# dds_ad9958.net
KiCad netlist of a schematic drawn in EAGLE
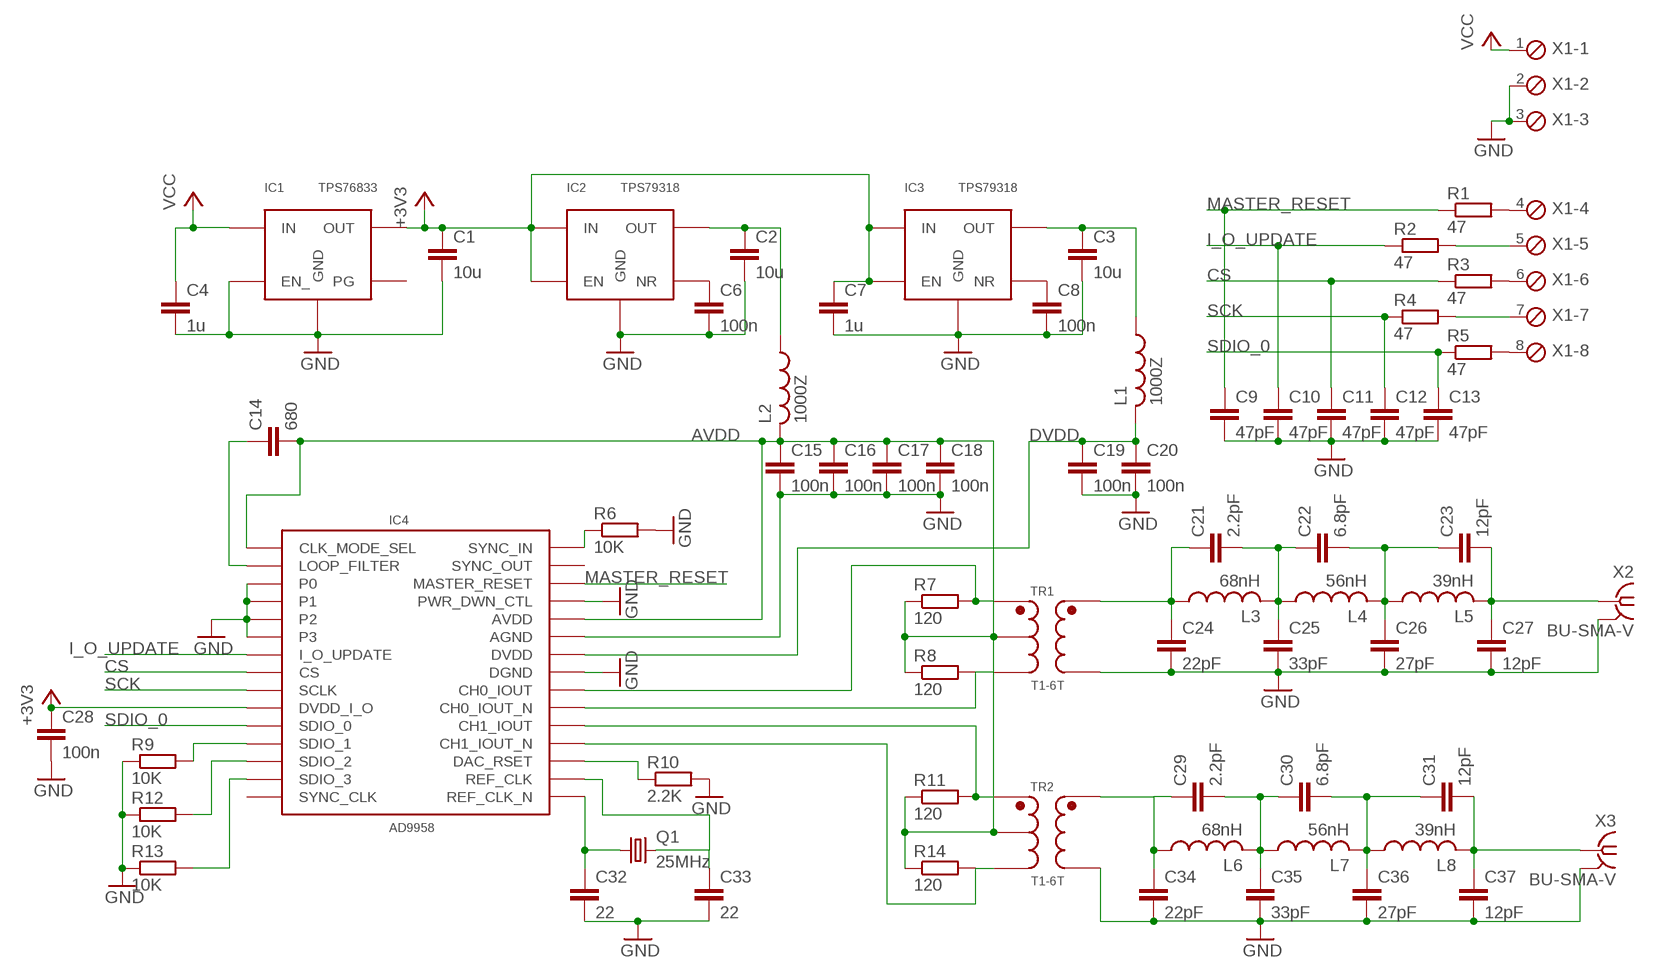
[diagram p0: schematic, sheet 1]

(export (version "E")
  (design (tool "Eeschema 10.0.6"))
  (components
    (comp (ref "C1")
      (value "10u")
      (footprint "eagle-import:C0805")
      (libsource (lib "eagle-import") (part "C-EUC0805"))
    )
    (comp (ref "C2")
      (value "10u")
      (footprint "eagle-import:C0805")
      (libsource (lib "eagle-import") (part "C-EUC0805"))
    )
    (comp (ref "C3")
      (value "10u")
      (footprint "eagle-import:C0805")
      (libsource (lib "eagle-import") (part "C-EUC0805"))
    )
    (comp (ref "C4")
      (value "1u")
      (footprint "eagle-import:C0603")
      (libsource (lib "eagle-import") (part "C-EUC0603"))
    )
    (comp (ref "C6")
      (value "100n")
      (footprint "eagle-import:C0603")
      (libsource (lib "eagle-import") (part "C-EUC0603"))
    )
    (comp (ref "C7")
      (value "1u")
      (footprint "eagle-import:C0603")
      (libsource (lib "eagle-import") (part "C-EUC0603"))
    )
    (comp (ref "C8")
      (value "100n")
      (footprint "eagle-import:C0603")
      (libsource (lib "eagle-import") (part "C-EUC0603"))
    )
    (comp (ref "C9")
      (value "47pF")
      (footprint "eagle-import:C0805")
      (libsource (lib "eagle-import") (part "C-EUC0805"))
    )
    (comp (ref "C10")
      (value "47pF")
      (footprint "eagle-import:C0805")
      (libsource (lib "eagle-import") (part "C-EUC0805"))
    )
    (comp (ref "C11")
      (value "47pF")
      (footprint "eagle-import:C0805")
      (libsource (lib "eagle-import") (part "C-EUC0805"))
    )
    (comp (ref "C12")
      (value "47pF")
      (footprint "eagle-import:C0805")
      (libsource (lib "eagle-import") (part "C-EUC0805"))
    )
    (comp (ref "C13")
      (value "47pF")
      (footprint "eagle-import:C0805")
      (libsource (lib "eagle-import") (part "C-EUC0805"))
    )
    (comp (ref "C14")
      (value "680")
      (footprint "eagle-import:C0805")
      (libsource (lib "eagle-import") (part "C-EUC0805"))
    )
    (comp (ref "C15")
      (value "100n")
      (footprint "eagle-import:C0603")
      (libsource (lib "eagle-import") (part "C-EUC0603"))
    )
    (comp (ref "C16")
      (value "100n")
      (footprint "eagle-import:C0603")
      (libsource (lib "eagle-import") (part "C-EUC0603"))
    )
    (comp (ref "C17")
      (value "100n")
      (footprint "eagle-import:C0603")
      (libsource (lib "eagle-import") (part "C-EUC0603"))
    )
    (comp (ref "C18")
      (value "100n")
      (footprint "eagle-import:C0603")
      (libsource (lib "eagle-import") (part "C-EUC0603"))
    )
    (comp (ref "C19")
      (value "100n")
      (footprint "eagle-import:C0603")
      (libsource (lib "eagle-import") (part "C-EUC0603"))
    )
    (comp (ref "C20")
      (value "100n")
      (footprint "eagle-import:C0603")
      (libsource (lib "eagle-import") (part "C-EUC0603"))
    )
    (comp (ref "C21")
      (value "2.2pF")
      (footprint "eagle-import:C0805")
      (libsource (lib "eagle-import") (part "C-EUC0805"))
    )
    (comp (ref "C22")
      (value "6.8pF")
      (footprint "eagle-import:C0805")
      (libsource (lib "eagle-import") (part "C-EUC0805"))
    )
    (comp (ref "C23")
      (value "12pF")
      (footprint "eagle-import:C0805")
      (libsource (lib "eagle-import") (part "C-EUC0805"))
    )
    (comp (ref "C24")
      (value "22pF")
      (footprint "eagle-import:C0805")
      (libsource (lib "eagle-import") (part "C-EUC0805"))
    )
    (comp (ref "C25")
      (value "33pF")
      (footprint "eagle-import:C0805")
      (libsource (lib "eagle-import") (part "C-EUC0805"))
    )
    (comp (ref "C26")
      (value "27pF")
      (footprint "eagle-import:C0805")
      (libsource (lib "eagle-import") (part "C-EUC0805"))
    )
    (comp (ref "C27")
      (value "12pF")
      (footprint "eagle-import:C0805")
      (libsource (lib "eagle-import") (part "C-EUC0805"))
    )
    (comp (ref "C28")
      (value "100n")
      (footprint "eagle-import:C0603")
      (libsource (lib "eagle-import") (part "C-EUC0603"))
    )
    (comp (ref "C29")
      (value "2.2pF")
      (footprint "eagle-import:C0805")
      (libsource (lib "eagle-import") (part "C-EUC0805"))
    )
    (comp (ref "C30")
      (value "6.8pF")
      (footprint "eagle-import:C0805")
      (libsource (lib "eagle-import") (part "C-EUC0805"))
    )
    (comp (ref "C31")
      (value "12pF")
      (footprint "eagle-import:C0805")
      (libsource (lib "eagle-import") (part "C-EUC0805"))
    )
    (comp (ref "C32")
      (value "22")
      (footprint "eagle-import:C0603")
      (libsource (lib "eagle-import") (part "C-EUC0603"))
    )
    (comp (ref "C33")
      (value "22")
      (footprint "eagle-import:C0603")
      (libsource (lib "eagle-import") (part "C-EUC0603"))
    )
    (comp (ref "C34")
      (value "22pF")
      (footprint "eagle-import:C0805")
      (libsource (lib "eagle-import") (part "C-EUC0805"))
    )
    (comp (ref "C35")
      (value "33pF")
      (footprint "eagle-import:C0805")
      (libsource (lib "eagle-import") (part "C-EUC0805"))
    )
    (comp (ref "C36")
      (value "27pF")
      (footprint "eagle-import:C0805")
      (libsource (lib "eagle-import") (part "C-EUC0805"))
    )
    (comp (ref "C37")
      (value "12pF")
      (footprint "eagle-import:C0805")
      (libsource (lib "eagle-import") (part "C-EUC0805"))
    )
    (comp (ref "IC1")
      (value "TPS76833")
      (footprint "eagle-import:SO8")
      (libsource (lib "eagle-import") (part "TPS768XX"))
    )
    (comp (ref "IC2")
      (value "TPS79318")
      (footprint "eagle-import:SOT23-5")
      (libsource (lib "eagle-import") (part "TPS793XX_FIXED"))
    )
    (comp (ref "IC3")
      (value "TPS79318")
      (footprint "eagle-import:SOT23-5")
      (libsource (lib "eagle-import") (part "TPS793XX_FIXED"))
    )
    (comp (ref "IC4")
      (value "AD9958")
      (footprint "eagle-import:CP-56-1")
      (libsource (lib "eagle-import") (part "AD9958"))
    )
    (comp (ref "L1")
      (value "1000Z")
      (footprint "eagle-import:L3225P")
      (libsource (lib "eagle-import") (part "L-USL3225P"))
    )
    (comp (ref "L2")
      (value "1000Z")
      (footprint "eagle-import:L3225P")
      (libsource (lib "eagle-import") (part "L-USL3225P"))
    )
    (comp (ref "L3")
      (value "68nH")
      (footprint "eagle-import:C0805")
      (libsource (lib "eagle-import") (part "L-USL0805"))
    )
    (comp (ref "L4")
      (value "56nH")
      (footprint "eagle-import:C0805")
      (libsource (lib "eagle-import") (part "L-USL0805"))
    )
    (comp (ref "L5")
      (value "39nH")
      (footprint "eagle-import:C0805")
      (libsource (lib "eagle-import") (part "L-USL0805"))
    )
    (comp (ref "L6")
      (value "68nH")
      (footprint "eagle-import:C0805")
      (libsource (lib "eagle-import") (part "L-USL0805"))
    )
    (comp (ref "L7")
      (value "56nH")
      (footprint "eagle-import:C0805")
      (libsource (lib "eagle-import") (part "L-USL0805"))
    )
    (comp (ref "L8")
      (value "39nH")
      (footprint "eagle-import:C0805")
      (libsource (lib "eagle-import") (part "L-USL0805"))
    )
    (comp (ref "Q1")
      (value "25MHz")
      (footprint "eagle-import:HC49_S")
      (libsource (lib "eagle-import") (part "CRYSTALHC49S"))
    )
    (comp (ref "R1")
      (value "47")
      (footprint "eagle-import:R0603")
      (libsource (lib "eagle-import") (part "R-EU_R0603"))
    )
    (comp (ref "R2")
      (value "47")
      (footprint "eagle-import:R0603")
      (libsource (lib "eagle-import") (part "R-EU_R0603"))
    )
    (comp (ref "R3")
      (value "47")
      (footprint "eagle-import:R0603")
      (libsource (lib "eagle-import") (part "R-EU_R0603"))
    )
    (comp (ref "R4")
      (value "47")
      (footprint "eagle-import:R0603")
      (libsource (lib "eagle-import") (part "R-EU_R0603"))
    )
    (comp (ref "R5")
      (value "47")
      (footprint "eagle-import:R0603")
      (libsource (lib "eagle-import") (part "R-EU_R0603"))
    )
    (comp (ref "R6")
      (value "10K")
      (footprint "eagle-import:R0603")
      (libsource (lib "eagle-import") (part "R-EU_R0603"))
    )
    (comp (ref "R7")
      (value "120")
      (footprint "eagle-import:R0603")
      (libsource (lib "eagle-import") (part "R-EU_R0603"))
    )
    (comp (ref "R8")
      (value "120")
      (footprint "eagle-import:R0603")
      (libsource (lib "eagle-import") (part "R-EU_R0603"))
    )
    (comp (ref "R9")
      (value "10K")
      (footprint "eagle-import:R0603")
      (libsource (lib "eagle-import") (part "R-EU_R0603"))
    )
    (comp (ref "R10")
      (value "2.2K")
      (footprint "eagle-import:R0603")
      (libsource (lib "eagle-import") (part "R-EU_R0603"))
    )
    (comp (ref "R11")
      (value "120")
      (footprint "eagle-import:R0603")
      (libsource (lib "eagle-import") (part "R-EU_R0603"))
    )
    (comp (ref "R12")
      (value "10K")
      (footprint "eagle-import:R0603")
      (libsource (lib "eagle-import") (part "R-EU_R0603"))
    )
    (comp (ref "R13")
      (value "10K")
      (footprint "eagle-import:R0603")
      (libsource (lib "eagle-import") (part "R-EU_R0603"))
    )
    (comp (ref "R14")
      (value "120")
      (footprint "eagle-import:R0603")
      (libsource (lib "eagle-import") (part "R-EU_R0603"))
    )
    (comp (ref "TR1")
      (value "T1-6T")
      (footprint "eagle-import:KK81")
      (libsource (lib "eagle-import") (part "T1-6T"))
    )
    (comp (ref "TR2")
      (value "T1-6T")
      (footprint "eagle-import:KK81")
      (libsource (lib "eagle-import") (part "T1-6T"))
    )
    (comp (ref "X1")
      (value "MPT8")
      (footprint "eagle-import:8POL254")
      (libsource (lib "eagle-import") (part "MPT8"))
    )
    (comp (ref "X2")
      (value "BU-SMA-V")
      (footprint "eagle-import:BU-SMA-V")
      (libsource (lib "eagle-import") (part "BU-SMA-V"))
    )
    (comp (ref "X3")
      (value "BU-SMA-V")
      (footprint "eagle-import:BU-SMA-V")
      (libsource (lib "eagle-import") (part "BU-SMA-V"))
    )
  )
  (nets
    (net (code "1") (name "+3V3") (class "Default")
      (node (ref "C1") (pin "1") (pinfunction "1_1") (pintype "passive"))
      (node (ref "C28") (pin "1") (pinfunction "1_1") (pintype "passive"))
      (node (ref "C7") (pin "1") (pinfunction "1_1") (pintype "passive"))
      (node (ref "IC1") (pin "5") (pinfunction "OUT_5") (pintype "bidirectional"))
      (node (ref "IC1") (pin "6") (pinfunction "OUT_6") (pintype "bidirectional"))
      (node (ref "IC2") (pin "1") (pinfunction "IN_1") (pintype "bidirectional"))
      (node (ref "IC2") (pin "3") (pinfunction "EN_3") (pintype "bidirectional"))
      (node (ref "IC3") (pin "1") (pinfunction "IN_1") (pintype "bidirectional"))
      (node (ref "IC3") (pin "3") (pinfunction "EN_3") (pintype "bidirectional"))
      (node (ref "IC4") (pin "P$49") (pinfunction "DVDD_I_O_P$49") (pintype "bidirectional"))
    )
    (net (code "2") (name "/AVDD") (class "Default")
      (node (ref "C14") (pin "2") (pinfunction "2_2") (pintype "passive"))
      (node (ref "C15") (pin "1") (pinfunction "1_1") (pintype "passive"))
      (node (ref "C16") (pin "1") (pinfunction "1_1") (pintype "passive"))
      (node (ref "C17") (pin "1") (pinfunction "1_1") (pintype "passive"))
      (node (ref "C18") (pin "1") (pinfunction "1_1") (pintype "passive"))
      (node (ref "IC4") (pin "P$11") (pinfunction "AVDD_P$11") (pintype "bidirectional"))
      (node (ref "IC4") (pin "P$15") (pinfunction "AVDD_P$15") (pintype "bidirectional"))
      (node (ref "IC4") (pin "P$19") (pinfunction "AVDD_P$19") (pintype "bidirectional"))
      (node (ref "IC4") (pin "P$21") (pinfunction "AVDD_P$21") (pintype "bidirectional"))
      (node (ref "IC4") (pin "P$24") (pinfunction "CLK_MODE_SEL_P$24") (pintype "bidirectional"))
      (node (ref "IC4") (pin "P$26") (pinfunction "AVDD_P$26") (pintype "bidirectional"))
      (node (ref "IC4") (pin "P$29") (pinfunction "AVDD_P$29") (pintype "bidirectional"))
      (node (ref "IC4") (pin "P$30") (pinfunction "AVDD_P$30") (pintype "bidirectional"))
      (node (ref "IC4") (pin "P$31") (pinfunction "AVDD_P$31") (pintype "bidirectional"))
      (node (ref "IC4") (pin "P$33") (pinfunction "AVDD_P$33") (pintype "bidirectional"))
      (node (ref "IC4") (pin "P$35") (pinfunction "AVDD_P$35") (pintype "bidirectional"))
      (node (ref "IC4") (pin "P$36") (pinfunction "AVDD_P$36") (pintype "bidirectional"))
      (node (ref "IC4") (pin "P$37") (pinfunction "AVDD_P$37") (pintype "bidirectional"))
      (node (ref "IC4") (pin "P$39") (pinfunction "AVDD_P$39") (pintype "bidirectional"))
      (node (ref "IC4") (pin "P$5") (pinfunction "AVDD_P$5") (pintype "bidirectional"))
      (node (ref "IC4") (pin "P$7") (pinfunction "AVDD_P$7") (pintype "bidirectional"))
      (node (ref "L2") (pin "2") (pinfunction "2_2") (pintype "passive"))
      (node (ref "R11") (pin "1") (pinfunction "1_1") (pintype "passive"))
      (node (ref "R14") (pin "1") (pinfunction "1_1") (pintype "passive"))
      (node (ref "R7") (pin "1") (pinfunction "1_1") (pintype "passive"))
      (node (ref "R8") (pin "1") (pinfunction "1_1") (pintype "passive"))
      (node (ref "TR1") (pin "P$2") (pinfunction "SEC_CT_P$2") (pintype "bidirectional"))
      (node (ref "TR2") (pin "P$2") (pinfunction "SEC_CT_P$2") (pintype "bidirectional"))
    )
    (net (code "3") (name "/CS") (class "Default")
      (node (ref "C11") (pin "1") (pinfunction "1_1") (pintype "passive"))
      (node (ref "IC4") (pin "P$47") (pinfunction "CS_P$47") (pintype "bidirectional"))
      (node (ref "R3") (pin "1") (pinfunction "1_1") (pintype "passive"))
    )
    (net (code "4") (name "/DVDD") (class "Default")
      (node (ref "C19") (pin "1") (pinfunction "1_1") (pintype "passive"))
      (node (ref "C20") (pin "1") (pinfunction "1_1") (pintype "passive"))
      (node (ref "IC4") (pin "P$45") (pinfunction "DVDD_P$45") (pintype "bidirectional"))
      (node (ref "IC4") (pin "P$55") (pinfunction "DVDD_P$55") (pintype "bidirectional"))
      (node (ref "L1") (pin "2") (pinfunction "2_2") (pintype "passive"))
    )
    (net (code "5") (name "/I_O_UPDATE") (class "Default")
      (node (ref "C10") (pin "1") (pinfunction "1_1") (pintype "passive"))
      (node (ref "IC4") (pin "P$46") (pinfunction "I_O_UPDATE_P$46") (pintype "bidirectional"))
      (node (ref "R2") (pin "1") (pinfunction "1_1") (pintype "passive"))
    )
    (net (code "6") (name "/MASTER_RESET") (class "Default")
      (node (ref "C9") (pin "1") (pinfunction "1_1") (pintype "passive"))
      (node (ref "IC4") (pin "P$3") (pinfunction "MASTER_RESET_P$3") (pintype "bidirectional"))
      (node (ref "R1") (pin "1") (pinfunction "1_1") (pintype "passive"))
    )
    (net (code "7") (name "/SCK") (class "Default")
      (node (ref "C12") (pin "1") (pinfunction "1_1") (pintype "passive"))
      (node (ref "IC4") (pin "P$48") (pinfunction "SCLK_P$48") (pintype "bidirectional"))
      (node (ref "R4") (pin "1") (pinfunction "1_1") (pintype "passive"))
    )
    (net (code "8") (name "/SDIO_0") (class "Default")
      (node (ref "C13") (pin "1") (pinfunction "1_1") (pintype "passive"))
      (node (ref "IC4") (pin "P$50") (pinfunction "SDIO_0_P$50") (pintype "bidirectional"))
      (node (ref "R5") (pin "1") (pinfunction "1_1") (pintype "passive"))
    )
    (net (code "9") (name "GND") (class "Default")
      (node (ref "C1") (pin "2") (pinfunction "2_2") (pintype "passive"))
      (node (ref "C10") (pin "2") (pinfunction "2_2") (pintype "passive"))
      (node (ref "C11") (pin "2") (pinfunction "2_2") (pintype "passive"))
      (node (ref "C12") (pin "2") (pinfunction "2_2") (pintype "passive"))
      (node (ref "C13") (pin "2") (pinfunction "2_2") (pintype "passive"))
      (node (ref "C15") (pin "2") (pinfunction "2_2") (pintype "passive"))
      (node (ref "C16") (pin "2") (pinfunction "2_2") (pintype "passive"))
      (node (ref "C17") (pin "2") (pinfunction "2_2") (pintype "passive"))
      (node (ref "C18") (pin "2") (pinfunction "2_2") (pintype "passive"))
      (node (ref "C19") (pin "2") (pinfunction "2_2") (pintype "passive"))
      (node (ref "C2") (pin "2") (pinfunction "2_2") (pintype "passive"))
      (node (ref "C20") (pin "2") (pinfunction "2_2") (pintype "passive"))
      (node (ref "C24") (pin "2") (pinfunction "2_2") (pintype "passive"))
      (node (ref "C25") (pin "2") (pinfunction "2_2") (pintype "passive"))
      (node (ref "C26") (pin "2") (pinfunction "2_2") (pintype "passive"))
      (node (ref "C27") (pin "2") (pinfunction "2_2") (pintype "passive"))
      (node (ref "C28") (pin "2") (pinfunction "2_2") (pintype "passive"))
      (node (ref "C3") (pin "2") (pinfunction "2_2") (pintype "passive"))
      (node (ref "C32") (pin "2") (pinfunction "2_2") (pintype "passive"))
      (node (ref "C33") (pin "2") (pinfunction "2_2") (pintype "passive"))
      (node (ref "C34") (pin "2") (pinfunction "2_2") (pintype "passive"))
      (node (ref "C35") (pin "2") (pinfunction "2_2") (pintype "passive"))
      (node (ref "C36") (pin "2") (pinfunction "2_2") (pintype "passive"))
      (node (ref "C37") (pin "2") (pinfunction "2_2") (pintype "passive"))
      (node (ref "C4") (pin "2") (pinfunction "2_2") (pintype "passive"))
      (node (ref "C6") (pin "2") (pinfunction "2_2") (pintype "passive"))
      (node (ref "C7") (pin "2") (pinfunction "2_2") (pintype "passive"))
      (node (ref "C8") (pin "2") (pinfunction "2_2") (pintype "passive"))
      (node (ref "C9") (pin "2") (pinfunction "2_2") (pintype "passive"))
      (node (ref "IC1") (pin "1") (pinfunction "GND_1") (pintype "bidirectional"))
      (node (ref "IC1") (pin "2") (pinfunction "EN__2") (pintype "bidirectional"))
      (node (ref "IC2") (pin "2") (pinfunction "GND_2") (pintype "bidirectional"))
      (node (ref "IC3") (pin "2") (pinfunction "GND_2") (pintype "bidirectional"))
      (node (ref "IC4") (pin "P$10") (pinfunction "AGND_P$10") (pintype "bidirectional"))
      (node (ref "IC4") (pin "P$12") (pinfunction "AGND_P$12") (pintype "bidirectional"))
      (node (ref "IC4") (pin "P$16") (pinfunction "AGND_P$16") (pintype "bidirectional"))
      (node (ref "IC4") (pin "P$18") (pinfunction "AGND_P$18") (pintype "bidirectional"))
      (node (ref "IC4") (pin "P$20") (pinfunction "AGND_P$20") (pintype "bidirectional"))
      (node (ref "IC4") (pin "P$25") (pinfunction "AGND_P$25") (pintype "bidirectional"))
      (node (ref "IC4") (pin "P$4") (pinfunction "PWR_DWN_CTL_P$4") (pintype "bidirectional"))
      (node (ref "IC4") (pin "P$40") (pinfunction "P0_P$40") (pintype "bidirectional"))
      (node (ref "IC4") (pin "P$41") (pinfunction "P1_P$41") (pintype "bidirectional"))
      (node (ref "IC4") (pin "P$42") (pinfunction "P2_P$42") (pintype "bidirectional"))
      (node (ref "IC4") (pin "P$43") (pinfunction "P3_P$43") (pintype "bidirectional"))
      (node (ref "IC4") (pin "P$44") (pinfunction "DGND_P$44") (pintype "bidirectional"))
      (node (ref "IC4") (pin "P$56") (pinfunction "DGND_P$56") (pintype "bidirectional"))
      (node (ref "IC4") (pin "P$6") (pinfunction "AGND_P$6") (pintype "bidirectional"))
      (node (ref "IC4") (pin "PAD") (pinfunction "AGND_PAD") (pintype "bidirectional"))
      (node (ref "R10") (pin "2") (pinfunction "2_2") (pintype "passive"))
      (node (ref "R12") (pin "1") (pinfunction "1_1") (pintype "passive"))
      (node (ref "R13") (pin "1") (pinfunction "1_1") (pintype "passive"))
      (node (ref "R6") (pin "2") (pinfunction "2_2") (pintype "passive"))
      (node (ref "R9") (pin "1") (pinfunction "1_1") (pintype "passive"))
      (node (ref "TR1") (pin "P$6") (pinfunction "PRI_P$6") (pintype "bidirectional"))
      (node (ref "TR2") (pin "P$6") (pinfunction "PRI_P$6") (pintype "bidirectional"))
      (node (ref "X1") (pin "2") (pinfunction "1_2") (pintype "passive"))
      (node (ref "X1") (pin "3") (pinfunction "1_3") (pintype "passive"))
      (node (ref "X2") (pin "2") (pinfunction "2_2") (pintype "passive"))
      (node (ref "X2") (pin "3") (pinfunction "2_3") (pintype "passive"))
      (node (ref "X2") (pin "4") (pinfunction "2_4") (pintype "passive"))
      (node (ref "X2") (pin "5") (pinfunction "2_5") (pintype "passive"))
      (node (ref "X3") (pin "2") (pinfunction "2_2") (pintype "passive"))
      (node (ref "X3") (pin "3") (pinfunction "2_3") (pintype "passive"))
      (node (ref "X3") (pin "4") (pinfunction "2_4") (pintype "passive"))
      (node (ref "X3") (pin "5") (pinfunction "2_5") (pintype "passive"))
    )
    (net (code "10") (name "Net-(C21-Pad2)") (class "Default")
      (node (ref "C21") (pin "2") (pinfunction "2_2") (pintype "passive"))
      (node (ref "C22") (pin "1") (pinfunction "1_1") (pintype "passive"))
      (node (ref "C25") (pin "1") (pinfunction "1_1") (pintype "passive"))
      (node (ref "L3") (pin "2") (pinfunction "2_2") (pintype "passive"))
      (node (ref "L4") (pin "1") (pinfunction "1_1") (pintype "passive"))
    )
    (net (code "11") (name "Net-(C22-Pad2)") (class "Default")
      (node (ref "C22") (pin "2") (pinfunction "2_2") (pintype "passive"))
      (node (ref "C23") (pin "1") (pinfunction "1_1") (pintype "passive"))
      (node (ref "C26") (pin "1") (pinfunction "1_1") (pintype "passive"))
      (node (ref "L4") (pin "2") (pinfunction "2_2") (pintype "passive"))
      (node (ref "L5") (pin "1") (pinfunction "1_1") (pintype "passive"))
    )
    (net (code "12") (name "Net-(C23-Pad2)") (class "Default")
      (node (ref "C23") (pin "2") (pinfunction "2_2") (pintype "passive"))
      (node (ref "C27") (pin "1") (pinfunction "1_1") (pintype "passive"))
      (node (ref "L5") (pin "2") (pinfunction "2_2") (pintype "passive"))
      (node (ref "X2") (pin "1") (pinfunction "1_1") (pintype "passive"))
    )
    (net (code "13") (name "Net-(C29-Pad2)") (class "Default")
      (node (ref "C29") (pin "2") (pinfunction "2_2") (pintype "passive"))
      (node (ref "C30") (pin "1") (pinfunction "1_1") (pintype "passive"))
      (node (ref "C35") (pin "1") (pinfunction "1_1") (pintype "passive"))
      (node (ref "L6") (pin "2") (pinfunction "2_2") (pintype "passive"))
      (node (ref "L7") (pin "1") (pinfunction "1_1") (pintype "passive"))
    )
    (net (code "14") (name "Net-(C30-Pad2)") (class "Default")
      (node (ref "C30") (pin "2") (pinfunction "2_2") (pintype "passive"))
      (node (ref "C31") (pin "1") (pinfunction "1_1") (pintype "passive"))
      (node (ref "C36") (pin "1") (pinfunction "1_1") (pintype "passive"))
      (node (ref "L7") (pin "2") (pinfunction "2_2") (pintype "passive"))
      (node (ref "L8") (pin "1") (pinfunction "1_1") (pintype "passive"))
    )
    (net (code "15") (name "Net-(C31-Pad2)") (class "Default")
      (node (ref "C31") (pin "2") (pinfunction "2_2") (pintype "passive"))
      (node (ref "C37") (pin "1") (pinfunction "1_1") (pintype "passive"))
      (node (ref "L8") (pin "2") (pinfunction "2_2") (pintype "passive"))
      (node (ref "X3") (pin "1") (pinfunction "1_1") (pintype "passive"))
    )
    (net (code "16") (name "Net-(IC2-NR)") (class "Default")
      (node (ref "C6") (pin "1") (pinfunction "1_1") (pintype "passive"))
      (node (ref "IC2") (pin "4") (pinfunction "NR_4") (pintype "bidirectional"))
    )
    (net (code "17") (name "Net-(IC2-OUT)") (class "Default")
      (node (ref "C2") (pin "1") (pinfunction "1_1") (pintype "passive"))
      (node (ref "IC2") (pin "5") (pinfunction "OUT_5") (pintype "bidirectional"))
      (node (ref "L2") (pin "1") (pinfunction "1_1") (pintype "passive"))
    )
    (net (code "18") (name "Net-(IC3-NR)") (class "Default")
      (node (ref "C8") (pin "1") (pinfunction "1_1") (pintype "passive"))
      (node (ref "IC3") (pin "4") (pinfunction "NR_4") (pintype "bidirectional"))
    )
    (net (code "19") (name "Net-(IC3-OUT)") (class "Default")
      (node (ref "C3") (pin "1") (pinfunction "1_1") (pintype "passive"))
      (node (ref "IC3") (pin "5") (pinfunction "OUT_5") (pintype "bidirectional"))
      (node (ref "L1") (pin "1") (pinfunction "1_1") (pintype "passive"))
    )
    (net (code "20") (name "Net-(IC4-CH0_IOUT)") (class "Default")
      (node (ref "IC4") (pin "P$8") (pinfunction "CH0_IOUT_P$8") (pintype "bidirectional"))
      (node (ref "R7") (pin "2") (pinfunction "2_2") (pintype "passive"))
      (node (ref "TR1") (pin "P$3") (pinfunction "SEC_DOT_P$3") (pintype "bidirectional"))
    )
    (net (code "21") (name "Net-(IC4-CH0_IOUT_N)") (class "Default")
      (node (ref "IC4") (pin "P$9") (pinfunction "CH0_IOUT_N_P$9") (pintype "bidirectional"))
      (node (ref "R8") (pin "2") (pinfunction "2_2") (pintype "passive"))
      (node (ref "TR1") (pin "P$1") (pinfunction "SEC_P$1") (pintype "bidirectional"))
    )
    (net (code "22") (name "Net-(IC4-CH1_IOUT)") (class "Default")
      (node (ref "IC4") (pin "P$13") (pinfunction "CH1_IOUT_P$13") (pintype "bidirectional"))
      (node (ref "R11") (pin "2") (pinfunction "2_2") (pintype "passive"))
      (node (ref "TR2") (pin "P$3") (pinfunction "SEC_DOT_P$3") (pintype "bidirectional"))
    )
    (net (code "23") (name "Net-(IC4-CH1_IOUT_N)") (class "Default")
      (node (ref "IC4") (pin "P$14") (pinfunction "CH1_IOUT_N_P$14") (pintype "bidirectional"))
      (node (ref "R14") (pin "2") (pinfunction "2_2") (pintype "passive"))
      (node (ref "TR2") (pin "P$1") (pinfunction "SEC_P$1") (pintype "bidirectional"))
    )
    (net (code "24") (name "Net-(IC4-DAC_RSET)") (class "Default")
      (node (ref "IC4") (pin "P$17") (pinfunction "DAC_RSET_P$17") (pintype "bidirectional"))
      (node (ref "R10") (pin "1") (pinfunction "1_1") (pintype "passive"))
    )
    (net (code "25") (name "Net-(IC4-LOOP_FILTER)") (class "Default")
      (node (ref "C14") (pin "1") (pinfunction "1_1") (pintype "passive"))
      (node (ref "IC4") (pin "P$27") (pinfunction "LOOP_FILTER_P$27") (pintype "bidirectional"))
    )
    (net (code "26") (name "Net-(IC4-REF_CLK)") (class "Default")
      (node (ref "C33") (pin "1") (pinfunction "1_1") (pintype "passive"))
      (node (ref "IC4") (pin "P$23") (pinfunction "REF_CLK_P$23") (pintype "bidirectional"))
      (node (ref "Q1") (pin "2") (pinfunction "2_2") (pintype "passive"))
    )
    (net (code "27") (name "Net-(IC4-REF_CLK_N)") (class "Default")
      (node (ref "C32") (pin "1") (pinfunction "1_1") (pintype "passive"))
      (node (ref "IC4") (pin "P$22") (pinfunction "REF_CLK_N_P$22") (pintype "bidirectional"))
      (node (ref "Q1") (pin "1") (pinfunction "1_1") (pintype "passive"))
    )
    (net (code "28") (name "Net-(IC4-SDIO_1)") (class "Default")
      (node (ref "IC4") (pin "P$51") (pinfunction "SDIO_1_P$51") (pintype "bidirectional"))
      (node (ref "R9") (pin "2") (pinfunction "2_2") (pintype "passive"))
    )
    (net (code "29") (name "Net-(IC4-SDIO_2)") (class "Default")
      (node (ref "IC4") (pin "P$52") (pinfunction "SDIO_2_P$52") (pintype "bidirectional"))
      (node (ref "R12") (pin "2") (pinfunction "2_2") (pintype "passive"))
    )
    (net (code "30") (name "Net-(IC4-SDIO_3)") (class "Default")
      (node (ref "IC4") (pin "P$53") (pinfunction "SDIO_3_P$53") (pintype "bidirectional"))
      (node (ref "R13") (pin "2") (pinfunction "2_2") (pintype "passive"))
    )
    (net (code "31") (name "Net-(IC4-SYNC_IN)") (class "Default")
      (node (ref "IC4") (pin "P$1") (pinfunction "SYNC_IN_P$1") (pintype "bidirectional"))
      (node (ref "R6") (pin "1") (pinfunction "1_1") (pintype "passive"))
    )
    (net (code "32") (name "Net-(TR1-PRI_DOT)") (class "Default")
      (node (ref "C21") (pin "1") (pinfunction "1_1") (pintype "passive"))
      (node (ref "C24") (pin "1") (pinfunction "1_1") (pintype "passive"))
      (node (ref "L3") (pin "1") (pinfunction "1_1") (pintype "passive"))
      (node (ref "TR1") (pin "P$4") (pinfunction "PRI_DOT_P$4") (pintype "bidirectional"))
    )
    (net (code "33") (name "Net-(TR2-PRI_DOT)") (class "Default")
      (node (ref "C29") (pin "1") (pinfunction "1_1") (pintype "passive"))
      (node (ref "C34") (pin "1") (pinfunction "1_1") (pintype "passive"))
      (node (ref "L6") (pin "1") (pinfunction "1_1") (pintype "passive"))
      (node (ref "TR2") (pin "P$4") (pinfunction "PRI_DOT_P$4") (pintype "bidirectional"))
    )
    (net (code "34") (name "Net-(X1D-1)") (class "Default")
      (node (ref "R1") (pin "2") (pinfunction "2_2") (pintype "passive"))
      (node (ref "X1") (pin "4") (pinfunction "1_4") (pintype "passive"))
    )
    (net (code "35") (name "Net-(X1E-1)") (class "Default")
      (node (ref "R2") (pin "2") (pinfunction "2_2") (pintype "passive"))
      (node (ref "X1") (pin "5") (pinfunction "1_5") (pintype "passive"))
    )
    (net (code "36") (name "Net-(X1F-1)") (class "Default")
      (node (ref "R3") (pin "2") (pinfunction "2_2") (pintype "passive"))
      (node (ref "X1") (pin "6") (pinfunction "1_6") (pintype "passive"))
    )
    (net (code "37") (name "Net-(X1G-1)") (class "Default")
      (node (ref "R4") (pin "2") (pinfunction "2_2") (pintype "passive"))
      (node (ref "X1") (pin "7") (pinfunction "1_7") (pintype "passive"))
    )
    (net (code "38") (name "Net-(X1H-1)") (class "Default")
      (node (ref "R5") (pin "2") (pinfunction "2_2") (pintype "passive"))
      (node (ref "X1") (pin "8") (pinfunction "1_8") (pintype "passive"))
    )
    (net (code "39") (name "VCC") (class "Default")
      (node (ref "C4") (pin "1") (pinfunction "1_1") (pintype "passive"))
      (node (ref "IC1") (pin "3") (pinfunction "IN_3") (pintype "bidirectional"))
      (node (ref "IC1") (pin "4") (pinfunction "IN_4") (pintype "bidirectional"))
      (node (ref "X1") (pin "1") (pinfunction "1_1") (pintype "passive"))
    )
    (net (code "40") (name "unconnected-(IC1-PG-Pad8)") (class "Default")
      (node (ref "IC1") (pin "8") (pinfunction "PG_8") (pintype "bidirectional"))
    )
    (net (code "41") (name "unconnected-(IC4-SYNC_CLK-PadP$54)") (class "Default")
      (node (ref "IC4") (pin "P$54") (pinfunction "SYNC_CLK_P$54") (pintype "bidirectional"))
    )
    (net (code "42") (name "unconnected-(IC4-SYNC_OUT-PadP$2)") (class "Default")
      (node (ref "IC4") (pin "P$2") (pinfunction "SYNC_OUT_P$2") (pintype "bidirectional"))
    )
  )
)
